# H_bridge.net
KiCad netlist of a schematic drawn in Altium Designer
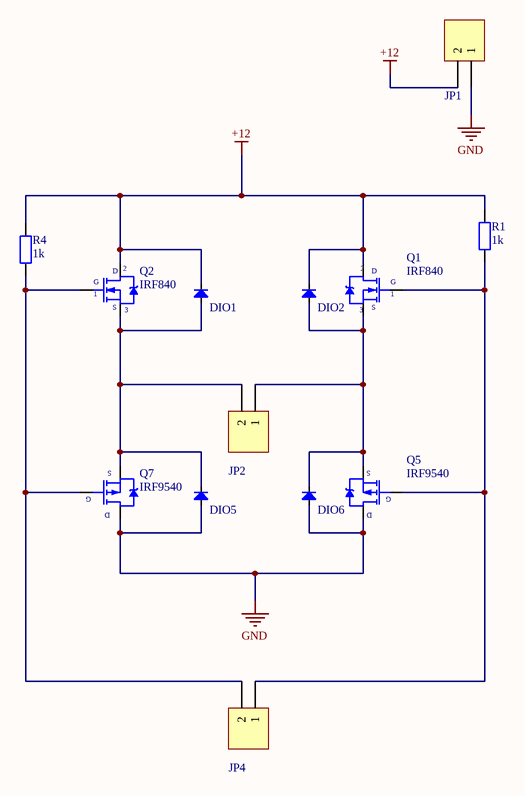
[diagram p0: H bridge.SchDoc]

(export (version "E")
  (design (tool "Eeschema 10.0.6"))
  (components
    (comp (ref "DIO1")
      (value "Diode SMD")
      (footprint "DIO-SMD-106")
      (description "Default Diode")
      (fields (field (name "PUBLISHER") "Altium Limited"))
      (libsource (lib "My Library") (part "Diode SMD"))
    )
    (comp (ref "DIO2")
      (value "Diode SMD")
      (footprint "DIO-SMD-106")
      (description "Default Diode")
      (fields (field (name "PUBLISHER") "Altium Limited"))
      (libsource (lib "My Library") (part "Diode SMD"))
    )
    (comp (ref "DIO5")
      (value "Diode SMD")
      (footprint "DIO-SMD-106")
      (description "Default Diode")
      (fields (field (name "PUBLISHER") "Altium Limited"))
      (libsource (lib "My Library") (part "Diode SMD"))
    )
    (comp (ref "DIO6")
      (value "Diode SMD")
      (footprint "DIO-SMD-106")
      (description "Default Diode")
      (fields (field (name "PUBLISHER") "Altium Limited"))
      (libsource (lib "My Library") (part "Diode SMD"))
    )
    (comp (ref "JP1")
      (value "Header 2_1")
      (footprint "HED2")
      (description "Header, 2-Pin")
      (fields (field (name "MANUFACTURER") "Generic Components"))
      (libsource (lib "") (part "Header 2_1_1"))
    )
    (comp (ref "JP2")
      (value "Header 2_1")
      (footprint "HED2")
      (description "Header, 2-Pin")
      (fields (field (name "MANUFACTURER") "Generic Components"))
      (libsource (lib "syhaunguyen") (part "Header 2_1"))
    )
    (comp (ref "JP4")
      (value "Header 2_1")
      (footprint "HED2")
      (description "Header, 2-Pin")
      (fields (field (name "MANUFACTURER") "Generic Components"))
      (libsource (lib "syhaunguyen") (part "Header 2_1"))
    )
    (comp (ref "Q1")
      (value "IRF840")
      (footprint "QTO-220")
      (description "MOSFET N - CHANNEL 500V - 0.75 - 8A - TO-220")
      (libsource (lib "syhaunguyen") (part "IRF840"))
    )
    (comp (ref "Q2")
      (value "IRF840")
      (footprint "QTO-220")
      (description "MOSFET N - CHANNEL 500V - 0.75 - 8A - TO-220")
      (libsource (lib "syhaunguyen") (part "IRF840"))
    )
    (comp (ref "Q5")
      (value "IRF9540")
      (footprint "QTO-220")
      (description "HEXFET P-Channel Power MOSFET")
      (fields (field (name "PUBLISHER") "Altium Limited"))
      (libsource (lib "My Library") (part "IRF9540"))
    )
    (comp (ref "Q7")
      (value "IRF9540")
      (footprint "QTO-220")
      (description "HEXFET P-Channel Power MOSFET")
      (fields (field (name "PUBLISHER") "Altium Limited"))
      (libsource (lib "My Library") (part "IRF9540"))
    )
    (comp (ref "R1")
      (value "1k")
      (footprint "R1/4W")
      (description "Resistor 1/4W")
      (libsource (lib "syhaunguyen") (part "R1/4W"))
    )
    (comp (ref "R4")
      (value "1k")
      (footprint "R1/4W")
      (description "Resistor 1/4W")
      (libsource (lib "syhaunguyen") (part "R1/4W"))
    )
  )
  (nets
    (net (code "1") (name "+12") (class "Default")
      (node (ref "DIO1") (pin "2") (pinfunction "K_2") (pintype "passive"))
      (node (ref "DIO2") (pin "2") (pinfunction "K_2") (pintype "passive"))
      (node (ref "JP1") (pin "2") (pinfunction "2_2") (pintype "passive"))
      (node (ref "Q1") (pin "2") (pinfunction "D_2") (pintype "passive"))
      (node (ref "Q2") (pin "2") (pinfunction "D_2") (pintype "passive"))
      (node (ref "R1") (pin "2") (pinfunction "2_2") (pintype "passive"))
      (node (ref "R4") (pin "2") (pinfunction "2_2") (pintype "passive"))
    )
    (net (code "2") (name "GND") (class "Default")
      (node (ref "DIO5") (pin "1") (pinfunction "A_1") (pintype "passive"))
      (node (ref "DIO6") (pin "1") (pinfunction "A_1") (pintype "passive"))
      (node (ref "JP1") (pin "1") (pinfunction "1_1") (pintype "passive"))
      (node (ref "Q5") (pin "2") (pinfunction "D_2") (pintype "passive"))
      (node (ref "Q7") (pin "2") (pinfunction "D_2") (pintype "passive"))
    )
    (net (code "3") (name "Net-(DIO1-A)") (class "Default")
      (node (ref "DIO1") (pin "1") (pinfunction "A_1") (pintype "passive"))
      (node (ref "DIO5") (pin "2") (pinfunction "K_2") (pintype "passive"))
      (node (ref "JP2") (pin "2") (pinfunction "2_2") (pintype "passive"))
      (node (ref "Q2") (pin "3") (pinfunction "S_3") (pintype "passive"))
      (node (ref "Q7") (pin "3") (pinfunction "S_3") (pintype "passive"))
    )
    (net (code "4") (name "Net-(DIO2-A)") (class "Default")
      (node (ref "DIO2") (pin "1") (pinfunction "A_1") (pintype "passive"))
      (node (ref "DIO6") (pin "2") (pinfunction "K_2") (pintype "passive"))
      (node (ref "JP2") (pin "1") (pinfunction "1_1") (pintype "passive"))
      (node (ref "Q1") (pin "3") (pinfunction "S_3") (pintype "passive"))
      (node (ref "Q5") (pin "3") (pinfunction "S_3") (pintype "passive"))
    )
    (net (code "5") (name "Net-(Q1-G)") (class "Default")
      (node (ref "JP4") (pin "1") (pinfunction "1_1") (pintype "passive"))
      (node (ref "Q1") (pin "1") (pinfunction "G_1") (pintype "passive"))
      (node (ref "Q5") (pin "1") (pinfunction "G_1") (pintype "passive"))
      (node (ref "R1") (pin "1") (pinfunction "1_1") (pintype "passive"))
    )
    (net (code "6") (name "Net-(Q2-G)") (class "Default")
      (node (ref "JP4") (pin "2") (pinfunction "2_2") (pintype "passive"))
      (node (ref "Q2") (pin "1") (pinfunction "G_1") (pintype "passive"))
      (node (ref "Q7") (pin "1") (pinfunction "G_1") (pintype "passive"))
      (node (ref "R4") (pin "1") (pinfunction "1_1") (pintype "passive"))
    )
  )
)
